# Controller.net
KiCad netlist of a schematic drawn in Altium Designer
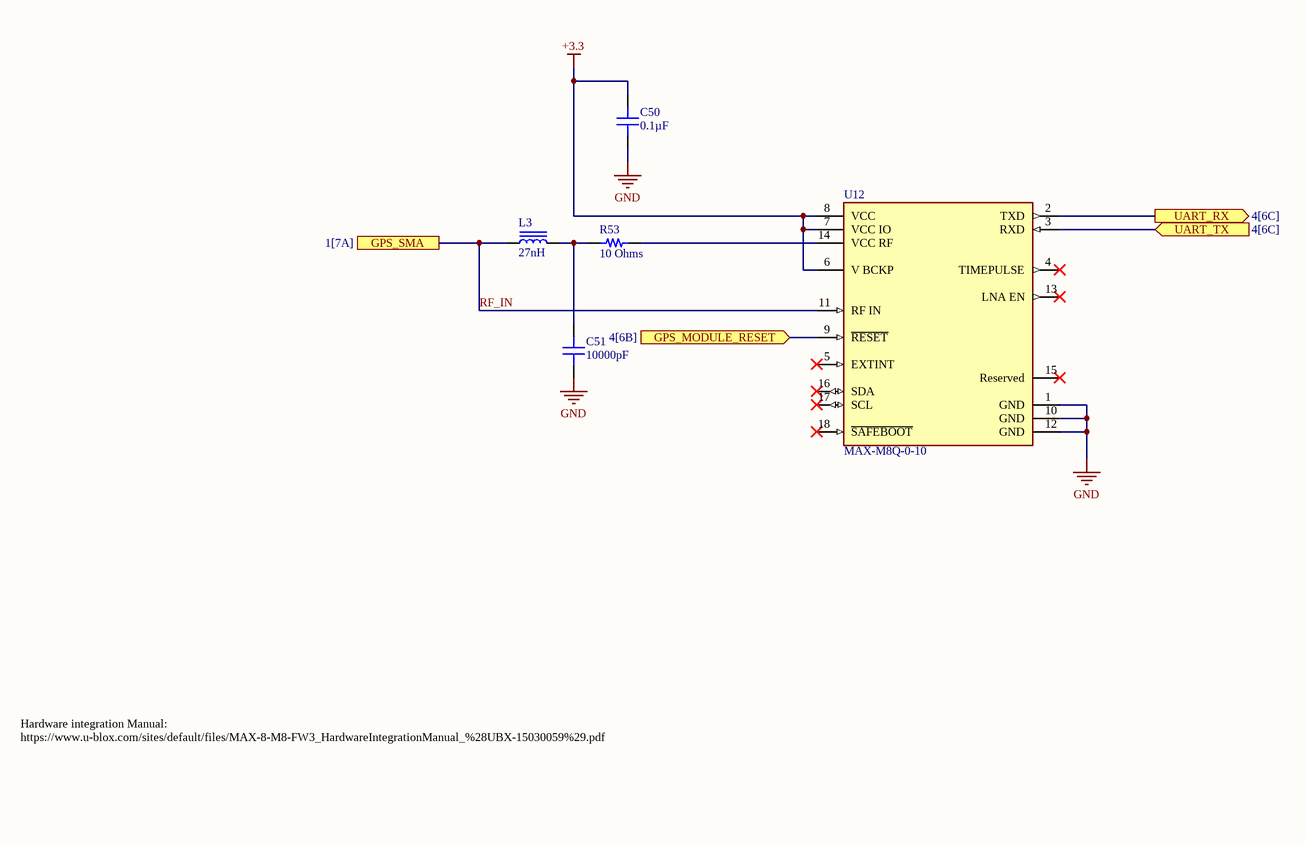
[diagram p0: Controller.SchDoc]

(export (version "E")
  (design (tool "Eeschema 10.0.6"))
  (components
    (comp (ref "C50")
      (value "0.1µF")
      (footprint "CAP 0603_1608")
      (description "CAP CER 0.1UF 25V X7R 0603")
      (fields
        (field (name "PART NUMBER") "CL10B104KA8WPNC")
        (field (name "MANUFACTURER") "Samsung Electro-Mechanics")
      )
      (libsource (lib "Celestial Altium Library - altium_library") (part "Capacitor"))
    )
    (comp (ref "C51")
      (value "10000pF")
      (footprint "CAP 0603_1608")
      (description "CAP CER 10000PF 16V X7R 0603")
      (fields (field (name "PART NUMBER") "C0603S103K4RACTU") (field (name "MANUFACTURER") "KEMET"))
      (libsource (lib "Celestial Altium Library - altium_library") (part "Capacitor"))
    )
    (comp (ref "L3")
      (value "27nH")
      (footprint "IND 0402_1005 RF WW")
      (description "FIXED IND 27NH 280MA 520 MOHM")
      (fields
        (field (name "PART NUMBER") "LQW15AN27NG00D")
        (field (name "MANUFACTURER") "Murata Electronics")
      )
      (libsource (lib "Celestial Altium Library - altium_library") (part "Inductor"))
    )
    (comp (ref "R53")
      (value "10 Ohms")
      (footprint "RES 0603_1608")
      (description "CRGCQ 0603 10R 1%")
      (fields
        (field (name "PART NUMBER") "CRGCQ0603F10R")
        (field (name "MANUFACTURER") "TE Connectivity Passive Product")
      )
      (libsource (lib "Celestial Altium Library - altium_library") (part "Resistor"))
    )
    (comp (ref "U12")
      (value "MAX-M8Q-0-10")
      (footprint "FP-MAX-M8Q-0-10-MFG")
      (description "RF RCVR GNSS/GPS 1.575GHZ 18LCC")
      (fields (field (name "MANUFACTURER") "u-blox") (field (name "MANUFACTURER PART NUMBER") "MAX-M8Q-0"))
      (libsource (lib "Altium Content Vault") (part "b2187b28c446abe4631fc0593d7d963"))
    )
  )
  (nets
    (net (code "1") (name "+3.3") (class "Default")
      (node (ref "C50") (pin "1") (pinfunction "1_1") (pintype "passive"))
      (node (ref "U12") (pin "6") (pinfunction "V_BCKP_6") (pintype "power_in"))
      (node (ref "U12") (pin "7") (pinfunction "VCC_IO_7") (pintype "power_in"))
      (node (ref "U12") (pin "8") (pinfunction "VCC_8") (pintype "power_in"))
    )
    (net (code "2") (name "/GPS_MODULE_RESET") (class "Default")
      (node (ref "U12") (pin "9") (pinfunction "~{RESET}_9") (pintype "input"))
    )
    (net (code "3") (name "/RF_IN") (class "Default")
      (node (ref "L3") (pin "1") (pinfunction "1_1") (pintype "passive"))
      (node (ref "U12") (pin "11") (pinfunction "RF_IN_11") (pintype "input"))
    )
    (net (code "4") (name "/UART_RX") (class "Default")
      (node (ref "U12") (pin "2") (pinfunction "TXD_2") (pintype "output"))
    )
    (net (code "5") (name "/UART_TX") (class "Default")
      (node (ref "U12") (pin "3") (pinfunction "RXD_3") (pintype "input"))
    )
    (net (code "6") (name "GND") (class "Default")
      (node (ref "C50") (pin "2") (pinfunction "2_2") (pintype "passive"))
      (node (ref "C51") (pin "1") (pinfunction "1_1") (pintype "passive"))
      (node (ref "U12") (pin "1") (pinfunction "GND_1") (pintype "power_in"))
      (node (ref "U12") (pin "10") (pinfunction "GND_10") (pintype "power_in"))
      (node (ref "U12") (pin "12") (pinfunction "GND_12") (pintype "power_in"))
    )
    (net (code "7") (name "Net-(C51-Pad2)") (class "Default")
      (node (ref "C51") (pin "2") (pinfunction "2_2") (pintype "passive"))
      (node (ref "L3") (pin "2") (pinfunction "2_2") (pintype "passive"))
      (node (ref "R53") (pin "2") (pinfunction "2_2") (pintype "passive"))
    )
    (net (code "8") (name "Net-(U12-VCC_RF)") (class "Default")
      (node (ref "R53") (pin "1") (pinfunction "1_1") (pintype "passive"))
      (node (ref "U12") (pin "14") (pinfunction "VCC_RF_14") (pintype "power_in"))
    )
    (net (code "9") (name "unconnected-(U12-EXTINT-Pad5)") (class "Default")
      (node (ref "U12") (pin "5") (pinfunction "EXTINT_5") (pintype "input+no_connect"))
    )
    (net (code "10") (name "unconnected-(U12-LNA_EN-Pad13)") (class "Default")
      (node (ref "U12") (pin "13") (pinfunction "LNA_EN_13") (pintype "output+no_connect"))
    )
    (net (code "11") (name "unconnected-(U12-Reserved-Pad15)") (class "Default")
      (node (ref "U12") (pin "15") (pinfunction "Reserved_15") (pintype "passive+no_connect"))
    )
    (net (code "12") (name "unconnected-(U12-SCL-Pad17)") (class "Default")
      (node (ref "U12") (pin "17") (pinfunction "SCL_17") (pintype "bidirectional+no_connect"))
    )
    (net (code "13") (name "unconnected-(U12-SDA-Pad16)") (class "Default")
      (node (ref "U12") (pin "16") (pinfunction "SDA_16") (pintype "bidirectional+no_connect"))
    )
    (net (code "14") (name "unconnected-(U12-TIMEPULSE-Pad4)") (class "Default")
      (node (ref "U12") (pin "4") (pinfunction "TIMEPULSE_4") (pintype "output+no_connect"))
    )
    (net (code "15") (name "unconnected-(U12-~{SAFEBOOT}-Pad18)") (class "Default")
      (node (ref "U12") (pin "18") (pinfunction "~{SAFEBOOT}_18") (pintype "input+no_connect"))
    )
  )
)
